# psx-mister.net
KiCad netlist of a schematic drawn in EAGLE
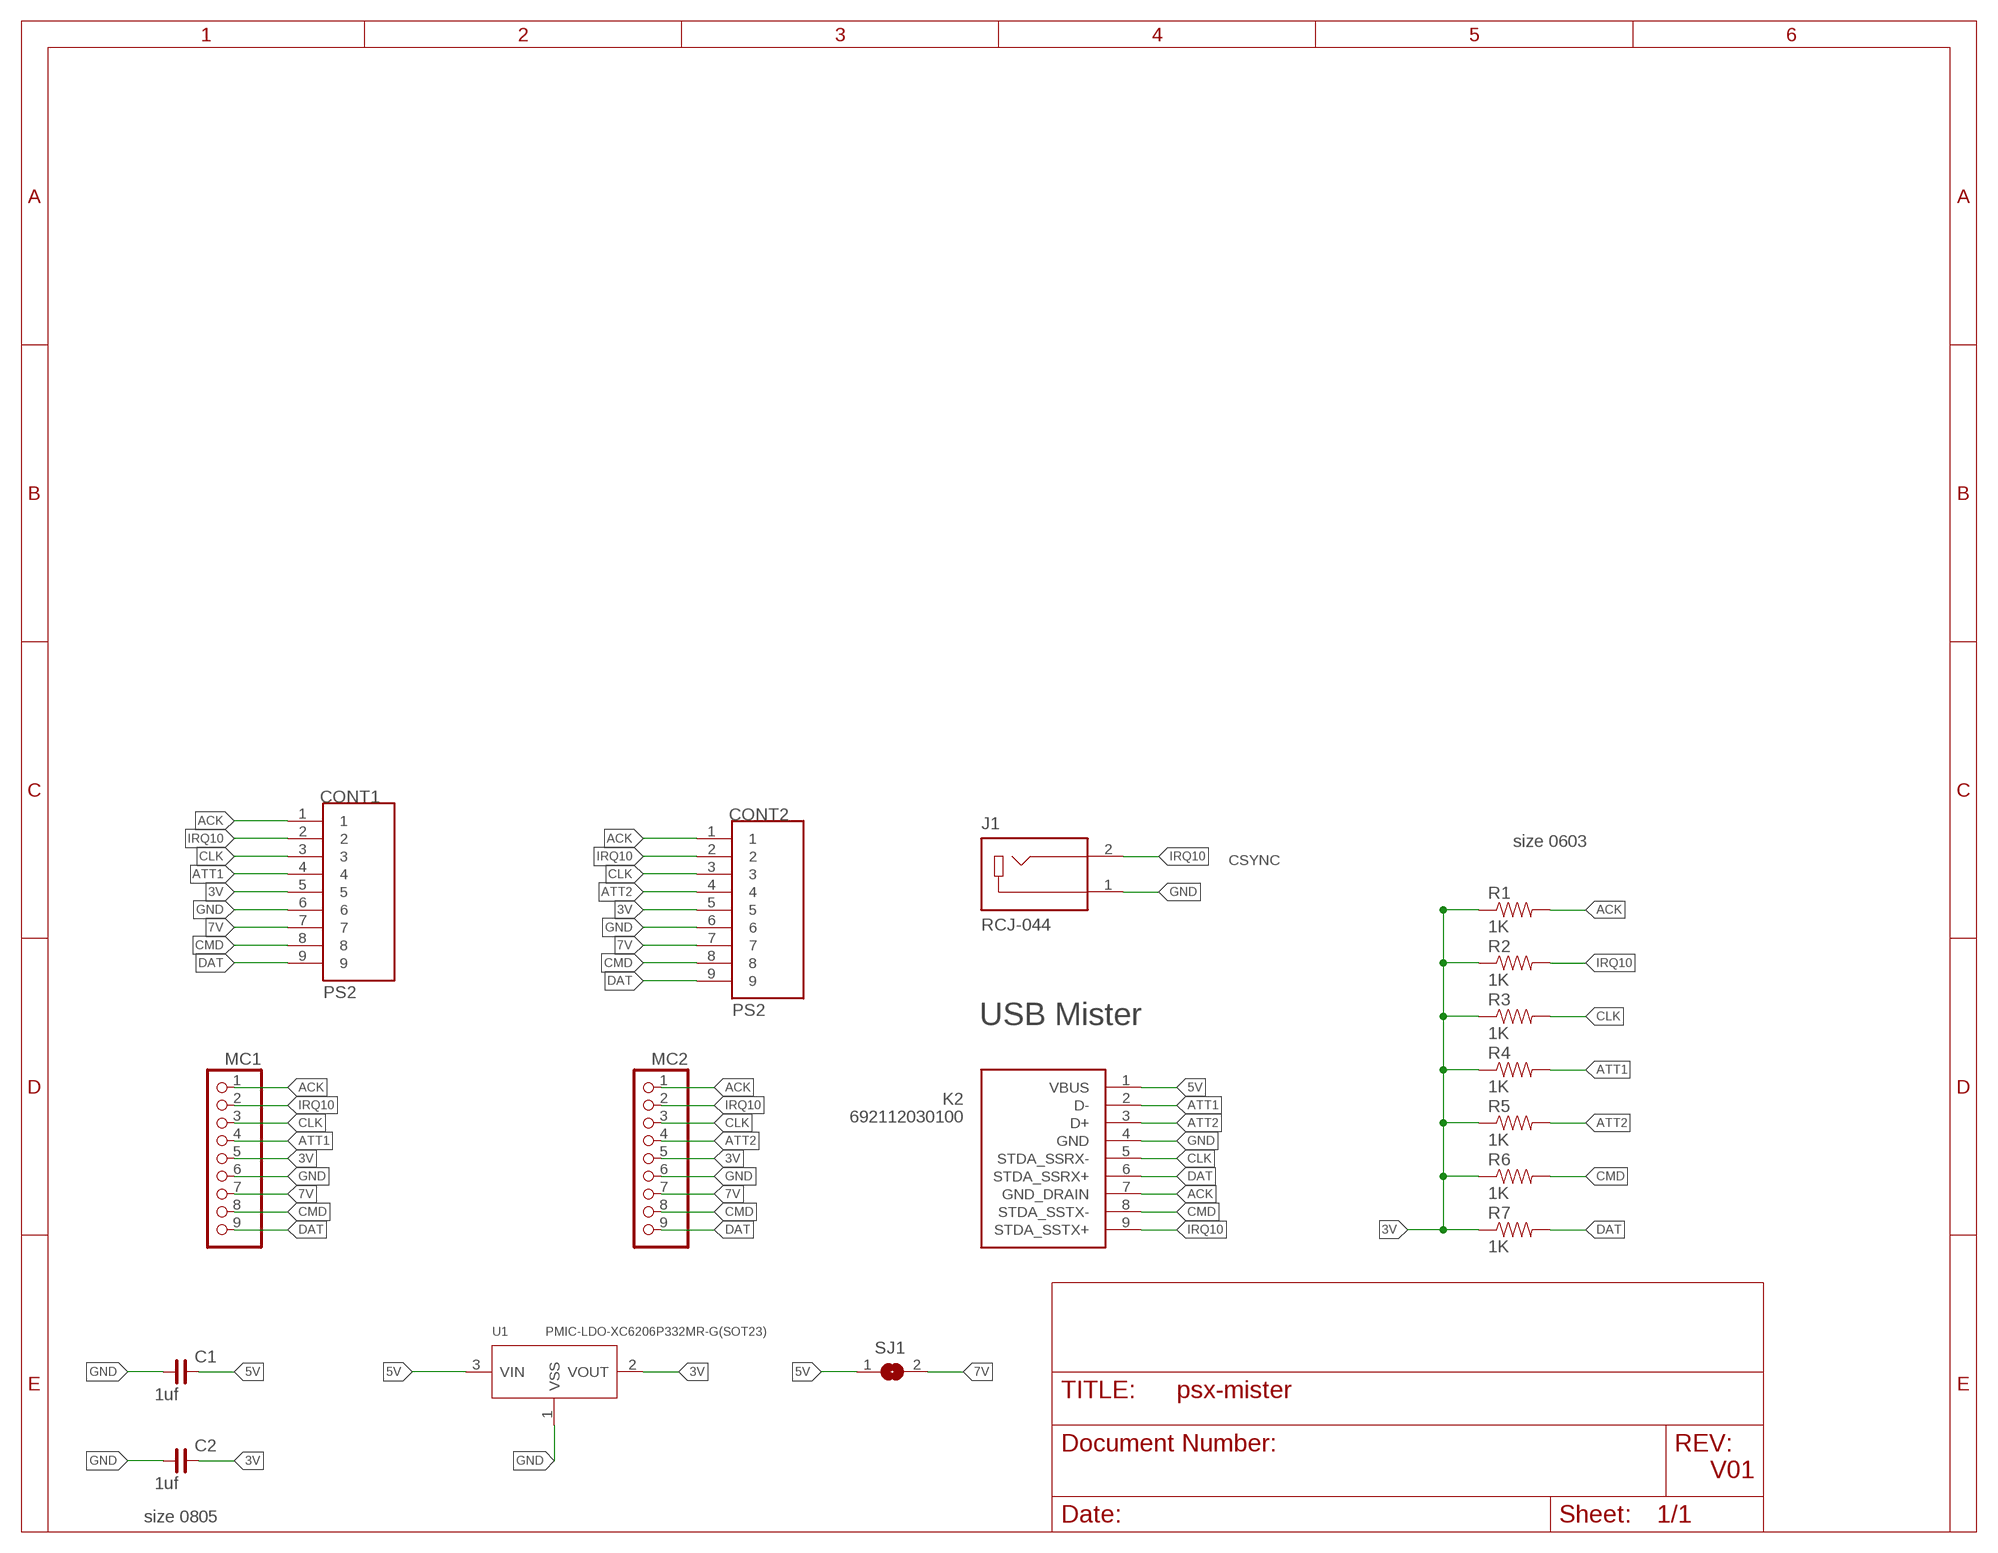
[diagram p0: schematic, sheet 1]

(export (version "E")
  (design (tool "Eeschema 10.0.6"))
  (components
    (comp (ref "C1")
      (value "1uf")
      (footprint "eagle-import:C0805")
      (libsource (lib "eagle-import") (part "C_0805"))
    )
    (comp (ref "C2")
      (value "1uf")
      (footprint "eagle-import:C0805")
      (libsource (lib "eagle-import") (part "C_0805"))
    )
    (comp (ref "CONT1")
      (value "PS2")
      (footprint "eagle-import:TE_PS2")
      (fields (field (name "MF") "TE Connectivity"))
      (libsource (lib "eagle-import") (part "PS2"))
    )
    (comp (ref "CONT2")
      (value "PS2")
      (footprint "eagle-import:TE_PS2")
      (fields (field (name "MF") "TE Connectivity"))
      (libsource (lib "eagle-import") (part "PS2"))
    )
    (comp (ref "J1")
      (value "RCJ-044")
      (footprint "eagle-import:CUI_RCJ-044")
      (fields (field (name "MF") "CUI Devices"))
      (libsource (lib "eagle-import") (part "RCJ-044"))
    )
    (comp (ref "K2")
      (value "692112030100")
      (footprint "eagle-import:692112030100")
      (libsource (lib "eagle-import") (part "692112030100"))
    )
    (comp (ref "MC1")
      (value "PINHD-1X09_2.54-S")
      (footprint "eagle-import:1X09-S")
      (libsource (lib "eagle-import") (part "PINHD-1X09_2.54-S"))
    )
    (comp (ref "MC2")
      (value "PINHD-1X09_2.54-S")
      (footprint "eagle-import:1X09-S")
      (libsource (lib "eagle-import") (part "PINHD-1X09_2.54-S"))
    )
    (comp (ref "R1")
      (value "1K")
      (footprint "eagle-import:0603-RES")
      (libsource (lib "eagle-import") (part "RESISTOR0603-RES"))
    )
    (comp (ref "R2")
      (value "1K")
      (footprint "eagle-import:0603-RES")
      (libsource (lib "eagle-import") (part "RESISTOR0603-RES"))
    )
    (comp (ref "R3")
      (value "1K")
      (footprint "eagle-import:0603-RES")
      (libsource (lib "eagle-import") (part "RESISTOR0603-RES"))
    )
    (comp (ref "R4")
      (value "1K")
      (footprint "eagle-import:0603-RES")
      (libsource (lib "eagle-import") (part "RESISTOR0603-RES"))
    )
    (comp (ref "R5")
      (value "1K")
      (footprint "eagle-import:0603-RES")
      (libsource (lib "eagle-import") (part "RESISTOR0603-RES"))
    )
    (comp (ref "R6")
      (value "1K")
      (footprint "eagle-import:0603-RES")
      (libsource (lib "eagle-import") (part "RESISTOR0603-RES"))
    )
    (comp (ref "R7")
      (value "1K")
      (footprint "eagle-import:0603-RES")
      (libsource (lib "eagle-import") (part "RESISTOR0603-RES"))
    )
    (comp (ref "SJ1") (value "SJ") (footprint "eagle-import:SJ") (libsource (lib "eagle-import") (part "SJ")))
    (comp (ref "U1")
      (value "PMIC-LDO-XC6206P332MR-G(SOT23)")
      (footprint "eagle-import:SOT-23")
      (fields (field (name "MF") "Torex") (field (name "MP") "XC6206P332MR-G"))
      (libsource (lib "eagle-import") (part "PMIC-LDO-XC6206P332MR-G(SOT23)"))
    )
  )
  (nets
    (net (code "1") (name "3V") (class "Default")
      (node (ref "C2") (pin "2") (pinfunction "2_2") (pintype "passive"))
      (node (ref "CONT1") (pin "5") (pinfunction "5_5") (pintype "passive"))
      (node (ref "CONT2") (pin "5") (pinfunction "5_5") (pintype "passive"))
      (node (ref "MC1") (pin "5") (pinfunction "5_5") (pintype "passive"))
      (node (ref "MC2") (pin "5") (pinfunction "5_5") (pintype "passive"))
      (node (ref "R1") (pin "1") (pinfunction "1_1") (pintype "passive"))
      (node (ref "R2") (pin "1") (pinfunction "1_1") (pintype "passive"))
      (node (ref "R3") (pin "1") (pinfunction "1_1") (pintype "passive"))
      (node (ref "R4") (pin "1") (pinfunction "1_1") (pintype "passive"))
      (node (ref "R5") (pin "1") (pinfunction "1_1") (pintype "passive"))
      (node (ref "R6") (pin "1") (pinfunction "1_1") (pintype "passive"))
      (node (ref "R7") (pin "1") (pinfunction "1_1") (pintype "passive"))
      (node (ref "U1") (pin "2") (pinfunction "VOUT_2") (pintype "output"))
    )
    (net (code "2") (name "5V") (class "Default")
      (node (ref "C1") (pin "2") (pinfunction "2_2") (pintype "passive"))
      (node (ref "K2") (pin "1") (pinfunction "VBUS_1") (pintype "bidirectional"))
      (node (ref "SJ1") (pin "1") (pinfunction "1_1") (pintype "passive"))
      (node (ref "U1") (pin "3") (pinfunction "VIN_3") (pintype "input"))
    )
    (net (code "3") (name "7V") (class "Default")
      (node (ref "CONT1") (pin "7") (pinfunction "7_7") (pintype "passive"))
      (node (ref "CONT2") (pin "7") (pinfunction "7_7") (pintype "passive"))
      (node (ref "MC1") (pin "7") (pinfunction "7_7") (pintype "passive"))
      (node (ref "MC2") (pin "7") (pinfunction "7_7") (pintype "passive"))
      (node (ref "SJ1") (pin "2") (pinfunction "2_2") (pintype "passive"))
    )
    (net (code "4") (name "ACK") (class "Default")
      (node (ref "CONT1") (pin "1") (pinfunction "1_1") (pintype "passive"))
      (node (ref "CONT2") (pin "1") (pinfunction "1_1") (pintype "passive"))
      (node (ref "K2") (pin "7") (pinfunction "GND_DRAIN_7") (pintype "bidirectional"))
      (node (ref "MC1") (pin "1") (pinfunction "1_1") (pintype "passive"))
      (node (ref "MC2") (pin "1") (pinfunction "1_1") (pintype "passive"))
      (node (ref "R1") (pin "2") (pinfunction "2_2") (pintype "passive"))
    )
    (net (code "5") (name "ATT1") (class "Default")
      (node (ref "CONT1") (pin "4") (pinfunction "4_4") (pintype "passive"))
      (node (ref "K2") (pin "2") (pinfunction "D-_2") (pintype "bidirectional"))
      (node (ref "MC1") (pin "4") (pinfunction "4_4") (pintype "passive"))
      (node (ref "R4") (pin "2") (pinfunction "2_2") (pintype "passive"))
    )
    (net (code "6") (name "ATT2") (class "Default")
      (node (ref "CONT2") (pin "4") (pinfunction "4_4") (pintype "passive"))
      (node (ref "K2") (pin "3") (pinfunction "D+_3") (pintype "bidirectional"))
      (node (ref "MC2") (pin "4") (pinfunction "4_4") (pintype "passive"))
      (node (ref "R5") (pin "2") (pinfunction "2_2") (pintype "passive"))
    )
    (net (code "7") (name "CLK") (class "Default")
      (node (ref "CONT1") (pin "3") (pinfunction "3_3") (pintype "passive"))
      (node (ref "CONT2") (pin "3") (pinfunction "3_3") (pintype "passive"))
      (node (ref "K2") (pin "5") (pinfunction "STDA_SSRX-_5") (pintype "bidirectional"))
      (node (ref "MC1") (pin "3") (pinfunction "3_3") (pintype "passive"))
      (node (ref "MC2") (pin "3") (pinfunction "3_3") (pintype "passive"))
      (node (ref "R3") (pin "2") (pinfunction "2_2") (pintype "passive"))
    )
    (net (code "8") (name "CMD") (class "Default")
      (node (ref "CONT1") (pin "8") (pinfunction "8_8") (pintype "passive"))
      (node (ref "CONT2") (pin "8") (pinfunction "8_8") (pintype "passive"))
      (node (ref "K2") (pin "8") (pinfunction "STDA_SSTX-_8") (pintype "bidirectional"))
      (node (ref "MC1") (pin "8") (pinfunction "8_8") (pintype "passive"))
      (node (ref "MC2") (pin "8") (pinfunction "8_8") (pintype "passive"))
      (node (ref "R6") (pin "2") (pinfunction "2_2") (pintype "passive"))
    )
    (net (code "9") (name "DAT") (class "Default")
      (node (ref "CONT1") (pin "9") (pinfunction "9_9") (pintype "passive"))
      (node (ref "CONT2") (pin "9") (pinfunction "9_9") (pintype "passive"))
      (node (ref "K2") (pin "6") (pinfunction "STDA_SSRX+_6") (pintype "bidirectional"))
      (node (ref "MC1") (pin "9") (pinfunction "9_9") (pintype "passive"))
      (node (ref "MC2") (pin "9") (pinfunction "9_9") (pintype "passive"))
      (node (ref "R7") (pin "2") (pinfunction "2_2") (pintype "passive"))
    )
    (net (code "10") (name "GND") (class "Default")
      (node (ref "C1") (pin "1") (pinfunction "1_1") (pintype "passive"))
      (node (ref "C2") (pin "1") (pinfunction "1_1") (pintype "passive"))
      (node (ref "CONT1") (pin "6") (pinfunction "6_6") (pintype "passive"))
      (node (ref "CONT2") (pin "6") (pinfunction "6_6") (pintype "passive"))
      (node (ref "J1") (pin "1") (pinfunction "1_1") (pintype "passive"))
      (node (ref "K2") (pin "4") (pinfunction "GND_4") (pintype "bidirectional"))
      (node (ref "MC1") (pin "6") (pinfunction "6_6") (pintype "passive"))
      (node (ref "MC2") (pin "6") (pinfunction "6_6") (pintype "passive"))
      (node (ref "U1") (pin "1") (pinfunction "VSS_1") (pintype "power_in"))
    )
    (net (code "11") (name "IRQ10") (class "Default")
      (node (ref "CONT1") (pin "2") (pinfunction "2_2") (pintype "passive"))
      (node (ref "CONT2") (pin "2") (pinfunction "2_2") (pintype "passive"))
      (node (ref "J1") (pin "2") (pinfunction "2_2") (pintype "passive"))
      (node (ref "K2") (pin "9") (pinfunction "STDA_SSTX+_9") (pintype "bidirectional"))
      (node (ref "MC1") (pin "2") (pinfunction "2_2") (pintype "passive"))
      (node (ref "MC2") (pin "2") (pinfunction "2_2") (pintype "passive"))
      (node (ref "R2") (pin "2") (pinfunction "2_2") (pintype "passive"))
    )
  )
)
